# pdb_v2.net
KiCad netlist of a schematic drawn in EAGLE
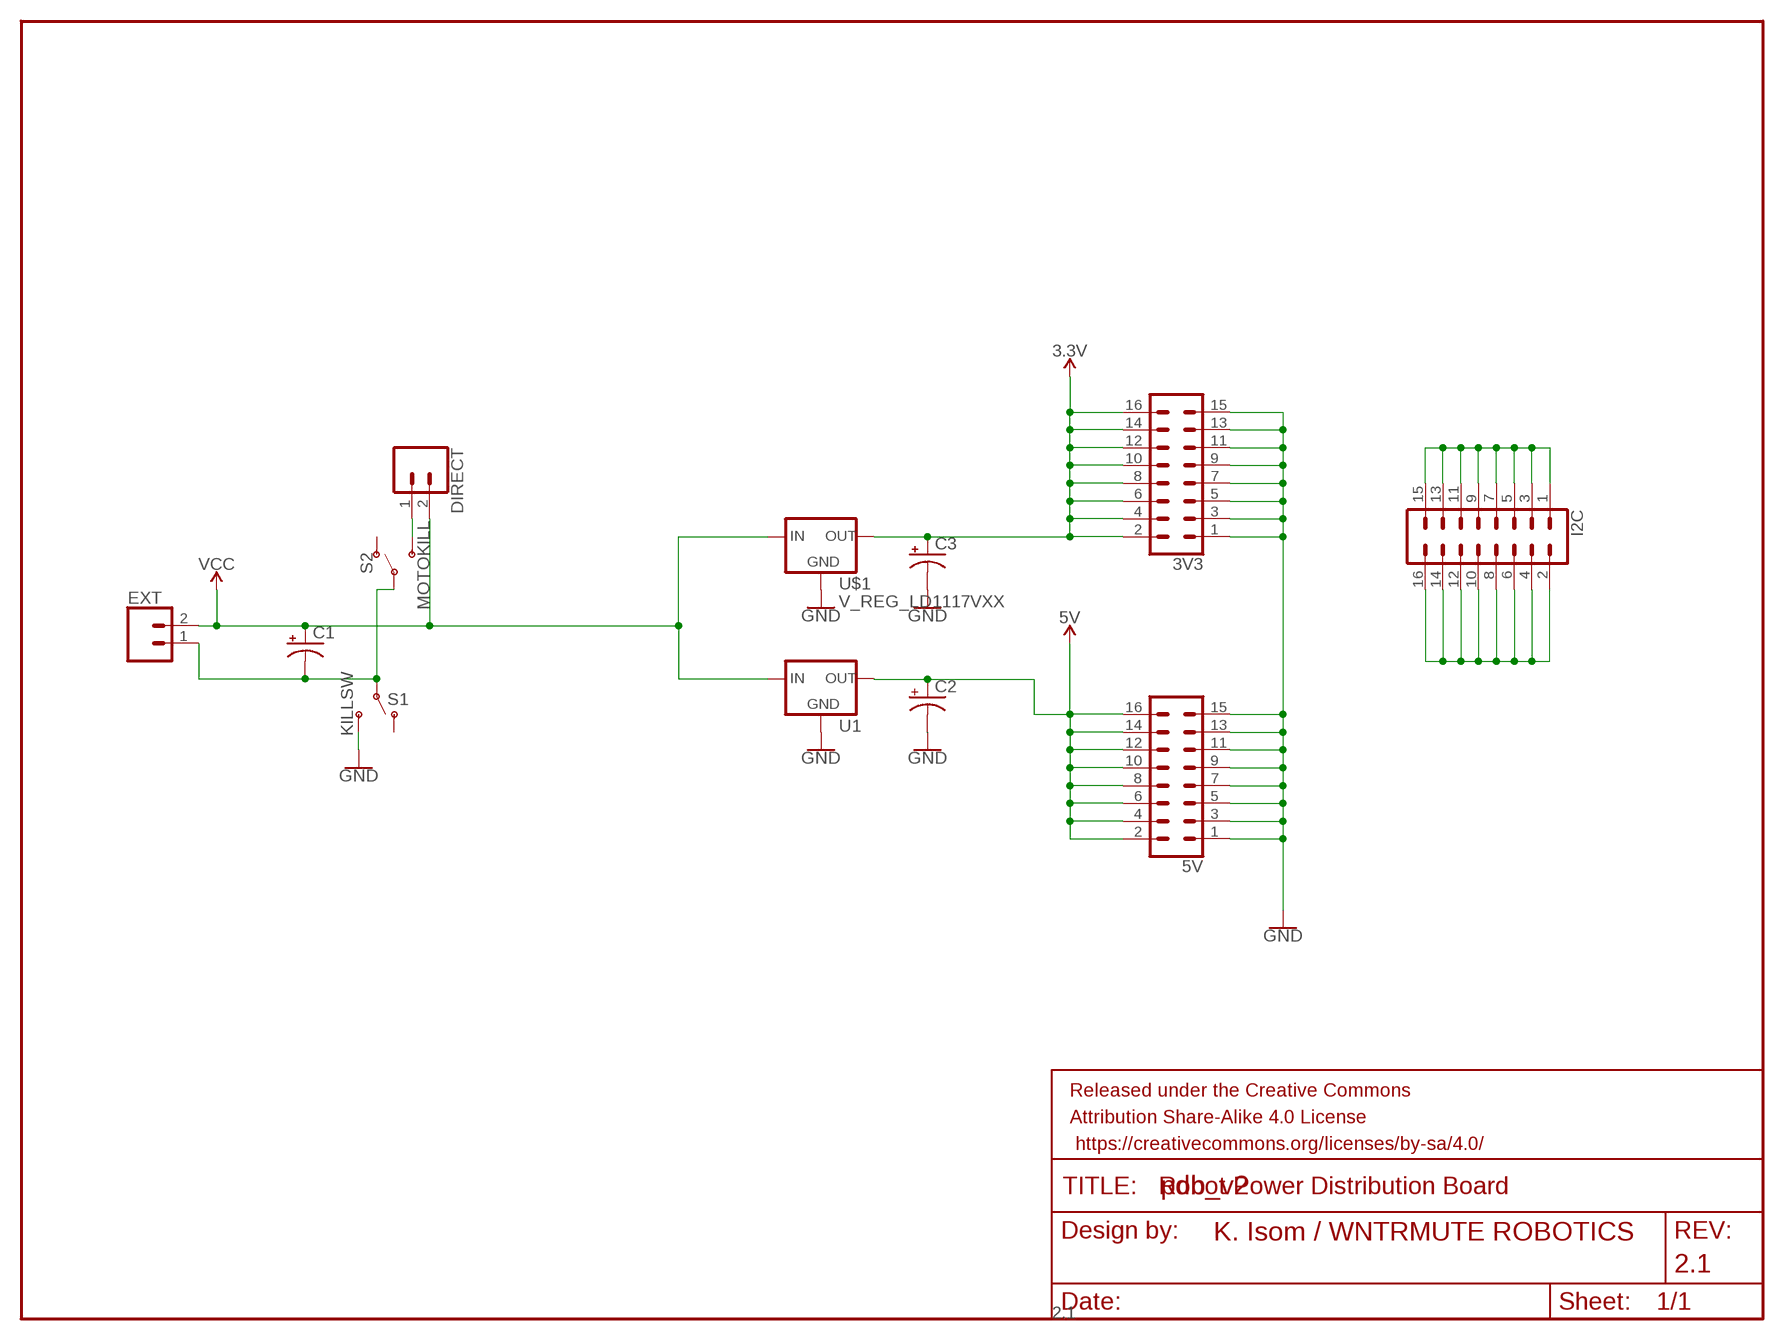
[diagram p0: schematic, sheet 1]

(export (version "E")
  (design (tool "Eeschema 10.0.6"))
  (components
    (comp (ref "3V3")
      (value "CONN_08X2_HEADER")
      (footprint "eagle-import:2X8")
      (libsource (lib "eagle-import") (part "CONN_08X2_HEADER"))
    )
    (comp (ref "5V")
      (value "CONN_08X2_HEADER")
      (footprint "eagle-import:2X8")
      (libsource (lib "eagle-import") (part "CONN_08X2_HEADER"))
    )
    (comp (ref "C1")
      (value "1000µF")
      (footprint "eagle-import:E5-10,5")
      (libsource (lib "eagle-import") (part "CPOL-USE5-10.5"))
    )
    (comp (ref "C2")
      (value "100uF")
      (footprint "eagle-import:E5-8,5")
      (libsource (lib "eagle-import") (part "CPOL-USE5-8.5"))
    )
    (comp (ref "C3")
      (value "100uF")
      (footprint "eagle-import:E5-8,5")
      (libsource (lib "eagle-import") (part "CPOL-USE5-8.5"))
    )
    (comp (ref "DIRECT")
      (value "CONN_025MM")
      (footprint "eagle-import:SCREWTERMINAL-5MM-2")
      (libsource (lib "eagle-import") (part "CONN_025MM"))
    )
    (comp (ref "EXT")
      (value "CONN_025MM")
      (footprint "eagle-import:SCREWTERMINAL-5MM-2")
      (libsource (lib "eagle-import") (part "CONN_025MM"))
    )
    (comp (ref "FRAME1")
      (value "FRAME-LETTERNO_PACKAGE")
      (footprint "eagle-import:DUMMY")
      (fields
        (field (name "DESIGNER") "K. Isom / WNTRMUTE ROBOTICS")
        (field (name "REV") "2.1")
        (field (name "VERSION") "2.1")
        (field (name "DESIGNER_1") "K. Isom / WNTRMUTE ROBOTICS")
        (field (name "VERSION_1") "2.1")
      )
      (libsource (lib "eagle-import") (part "FRAME-LETTERNO_PACKAGE"))
    )
    (comp (ref "I2C")
      (value "CONN_08X2_HEADER")
      (footprint "eagle-import:2X8")
      (libsource (lib "eagle-import") (part "CONN_08X2_HEADER"))
    )
    (comp (ref "S1")
      (value "KILLSW")
      (footprint "eagle-import:SWITCH_SPDT_PTH_11.6X4.0MM_LOCK")
      (libsource (lib "eagle-import") (part "SWITCH-SPDT-PTH-11.6X4.0MM-LOCK"))
    )
    (comp (ref "S2")
      (value "MOTOKILL")
      (footprint "eagle-import:SWITCH_SPDT_PTH_11.6X4.0MM_LOCK")
      (libsource (lib "eagle-import") (part "SWITCH-SPDT-PTH-11.6X4.0MM-LOCK"))
    )
    (comp (ref "U$1")
      (value "V_REG_LD1117VXX")
      (footprint "eagle-import:78XXL")
      (libsource (lib "eagle-import") (part "V_REG_LD1117VXX"))
    )
    (comp (ref "U1")
      (value "V_REG_78XX-TO-220")
      (footprint "eagle-import:TO-220-ALT")
      (libsource (lib "eagle-import") (part "V_REG_78XX-TO-220"))
    )
  )
  (nets
    (net (code "1") (name "3.3V") (class "Default")
      (node (ref "3V3") (pin "10") (pinfunction "10_10") (pintype "passive"))
      (node (ref "3V3") (pin "12") (pinfunction "12_12") (pintype "passive"))
      (node (ref "3V3") (pin "14") (pinfunction "14_14") (pintype "passive"))
      (node (ref "3V3") (pin "16") (pinfunction "16_16") (pintype "passive"))
      (node (ref "3V3") (pin "2") (pinfunction "2_2") (pintype "passive"))
      (node (ref "3V3") (pin "4") (pinfunction "4_4") (pintype "passive"))
      (node (ref "3V3") (pin "6") (pinfunction "6_6") (pintype "passive"))
      (node (ref "3V3") (pin "8") (pinfunction "8_8") (pintype "passive"))
      (node (ref "C3") (pin "+") (pinfunction "+_+") (pintype "passive"))
      (node (ref "U$1") (pin "GND") (pinfunction "OUT_GND") (pintype "passive"))
    )
    (net (code "2") (name "5V") (class "Default")
      (node (ref "5V") (pin "10") (pinfunction "10_10") (pintype "passive"))
      (node (ref "5V") (pin "12") (pinfunction "12_12") (pintype "passive"))
      (node (ref "5V") (pin "14") (pinfunction "14_14") (pintype "passive"))
      (node (ref "5V") (pin "16") (pinfunction "16_16") (pintype "passive"))
      (node (ref "5V") (pin "2") (pinfunction "2_2") (pintype "passive"))
      (node (ref "5V") (pin "4") (pinfunction "4_4") (pintype "passive"))
      (node (ref "5V") (pin "6") (pinfunction "6_6") (pintype "passive"))
      (node (ref "5V") (pin "8") (pinfunction "8_8") (pintype "passive"))
      (node (ref "C2") (pin "+") (pinfunction "+_+") (pintype "passive"))
      (node (ref "U1") (pin "OUT") (pinfunction "OUT_OUT") (pintype "passive"))
    )
    (net (code "3") (name "GND") (class "Default")
      (node (ref "3V3") (pin "1") (pinfunction "1_1") (pintype "passive"))
      (node (ref "3V3") (pin "11") (pinfunction "11_11") (pintype "passive"))
      (node (ref "3V3") (pin "13") (pinfunction "13_13") (pintype "passive"))
      (node (ref "3V3") (pin "15") (pinfunction "15_15") (pintype "passive"))
      (node (ref "3V3") (pin "3") (pinfunction "3_3") (pintype "passive"))
      (node (ref "3V3") (pin "5") (pinfunction "5_5") (pintype "passive"))
      (node (ref "3V3") (pin "7") (pinfunction "7_7") (pintype "passive"))
      (node (ref "3V3") (pin "9") (pinfunction "9_9") (pintype "passive"))
      (node (ref "5V") (pin "1") (pinfunction "1_1") (pintype "passive"))
      (node (ref "5V") (pin "11") (pinfunction "11_11") (pintype "passive"))
      (node (ref "5V") (pin "13") (pinfunction "13_13") (pintype "passive"))
      (node (ref "5V") (pin "15") (pinfunction "15_15") (pintype "passive"))
      (node (ref "5V") (pin "3") (pinfunction "3_3") (pintype "passive"))
      (node (ref "5V") (pin "5") (pinfunction "5_5") (pintype "passive"))
      (node (ref "5V") (pin "7") (pinfunction "7_7") (pintype "passive"))
      (node (ref "5V") (pin "9") (pinfunction "9_9") (pintype "passive"))
      (node (ref "C2") (pin "-") (pinfunction "-_-") (pintype "passive"))
      (node (ref "C3") (pin "-") (pinfunction "-_-") (pintype "passive"))
      (node (ref "S1") (pin "3") (pinfunction "S_3") (pintype "passive"))
      (node (ref "U$1") (pin "IN") (pinfunction "GND_IN") (pintype "input"))
      (node (ref "U1") (pin "GND") (pinfunction "GND_GND") (pintype "input"))
    )
    (net (code "4") (name "Net-(I2C-Pad1)") (class "Default")
      (node (ref "I2C") (pin "1") (pinfunction "1_1") (pintype "passive"))
      (node (ref "I2C") (pin "11") (pinfunction "11_11") (pintype "passive"))
      (node (ref "I2C") (pin "13") (pinfunction "13_13") (pintype "passive"))
      (node (ref "I2C") (pin "15") (pinfunction "15_15") (pintype "passive"))
      (node (ref "I2C") (pin "3") (pinfunction "3_3") (pintype "passive"))
      (node (ref "I2C") (pin "5") (pinfunction "5_5") (pintype "passive"))
      (node (ref "I2C") (pin "7") (pinfunction "7_7") (pintype "passive"))
      (node (ref "I2C") (pin "9") (pinfunction "9_9") (pintype "passive"))
    )
    (net (code "5") (name "Net-(I2C-Pad10)") (class "Default")
      (node (ref "I2C") (pin "10") (pinfunction "10_10") (pintype "passive"))
      (node (ref "I2C") (pin "12") (pinfunction "12_12") (pintype "passive"))
      (node (ref "I2C") (pin "14") (pinfunction "14_14") (pintype "passive"))
      (node (ref "I2C") (pin "16") (pinfunction "16_16") (pintype "passive"))
      (node (ref "I2C") (pin "2") (pinfunction "2_2") (pintype "passive"))
      (node (ref "I2C") (pin "4") (pinfunction "4_4") (pintype "passive"))
      (node (ref "I2C") (pin "6") (pinfunction "6_6") (pintype "passive"))
      (node (ref "I2C") (pin "8") (pinfunction "8_8") (pintype "passive"))
    )
    (net (code "6") (name "Net-(S1-P)") (class "Default")
      (node (ref "C1") (pin "-") (pinfunction "-_-") (pintype "passive"))
      (node (ref "EXT") (pin "1") (pinfunction "1_1") (pintype "passive"))
      (node (ref "S1") (pin "2") (pinfunction "P_2") (pintype "passive"))
      (node (ref "S2") (pin "2") (pinfunction "P_2") (pintype "passive"))
    )
    (net (code "7") (name "Net-(S2-S)") (class "Default")
      (node (ref "DIRECT") (pin "1") (pinfunction "1_1") (pintype "passive"))
      (node (ref "S2") (pin "3") (pinfunction "S_3") (pintype "passive"))
    )
    (net (code "8") (name "VCC") (class "Default")
      (node (ref "C1") (pin "+") (pinfunction "+_+") (pintype "passive"))
      (node (ref "DIRECT") (pin "2") (pinfunction "2_2") (pintype "passive"))
      (node (ref "EXT") (pin "2") (pinfunction "2_2") (pintype "passive"))
      (node (ref "U$1") (pin "OUT") (pinfunction "IN_OUT") (pintype "input"))
      (node (ref "U1") (pin "IN") (pinfunction "IN_IN") (pintype "input"))
    )
    (net (code "9") (name "unconnected-(S1-O-Pad1)") (class "Default")
      (node (ref "S1") (pin "1") (pinfunction "O_1") (pintype "passive"))
    )
    (net (code "10") (name "unconnected-(S2-O-Pad1)") (class "Default")
      (node (ref "S2") (pin "1") (pinfunction "O_1") (pintype "passive"))
    )
  )
)
